# IZU2023_computerboard_ver1.net
KiCad netlist of a schematic drawn in EAGLE
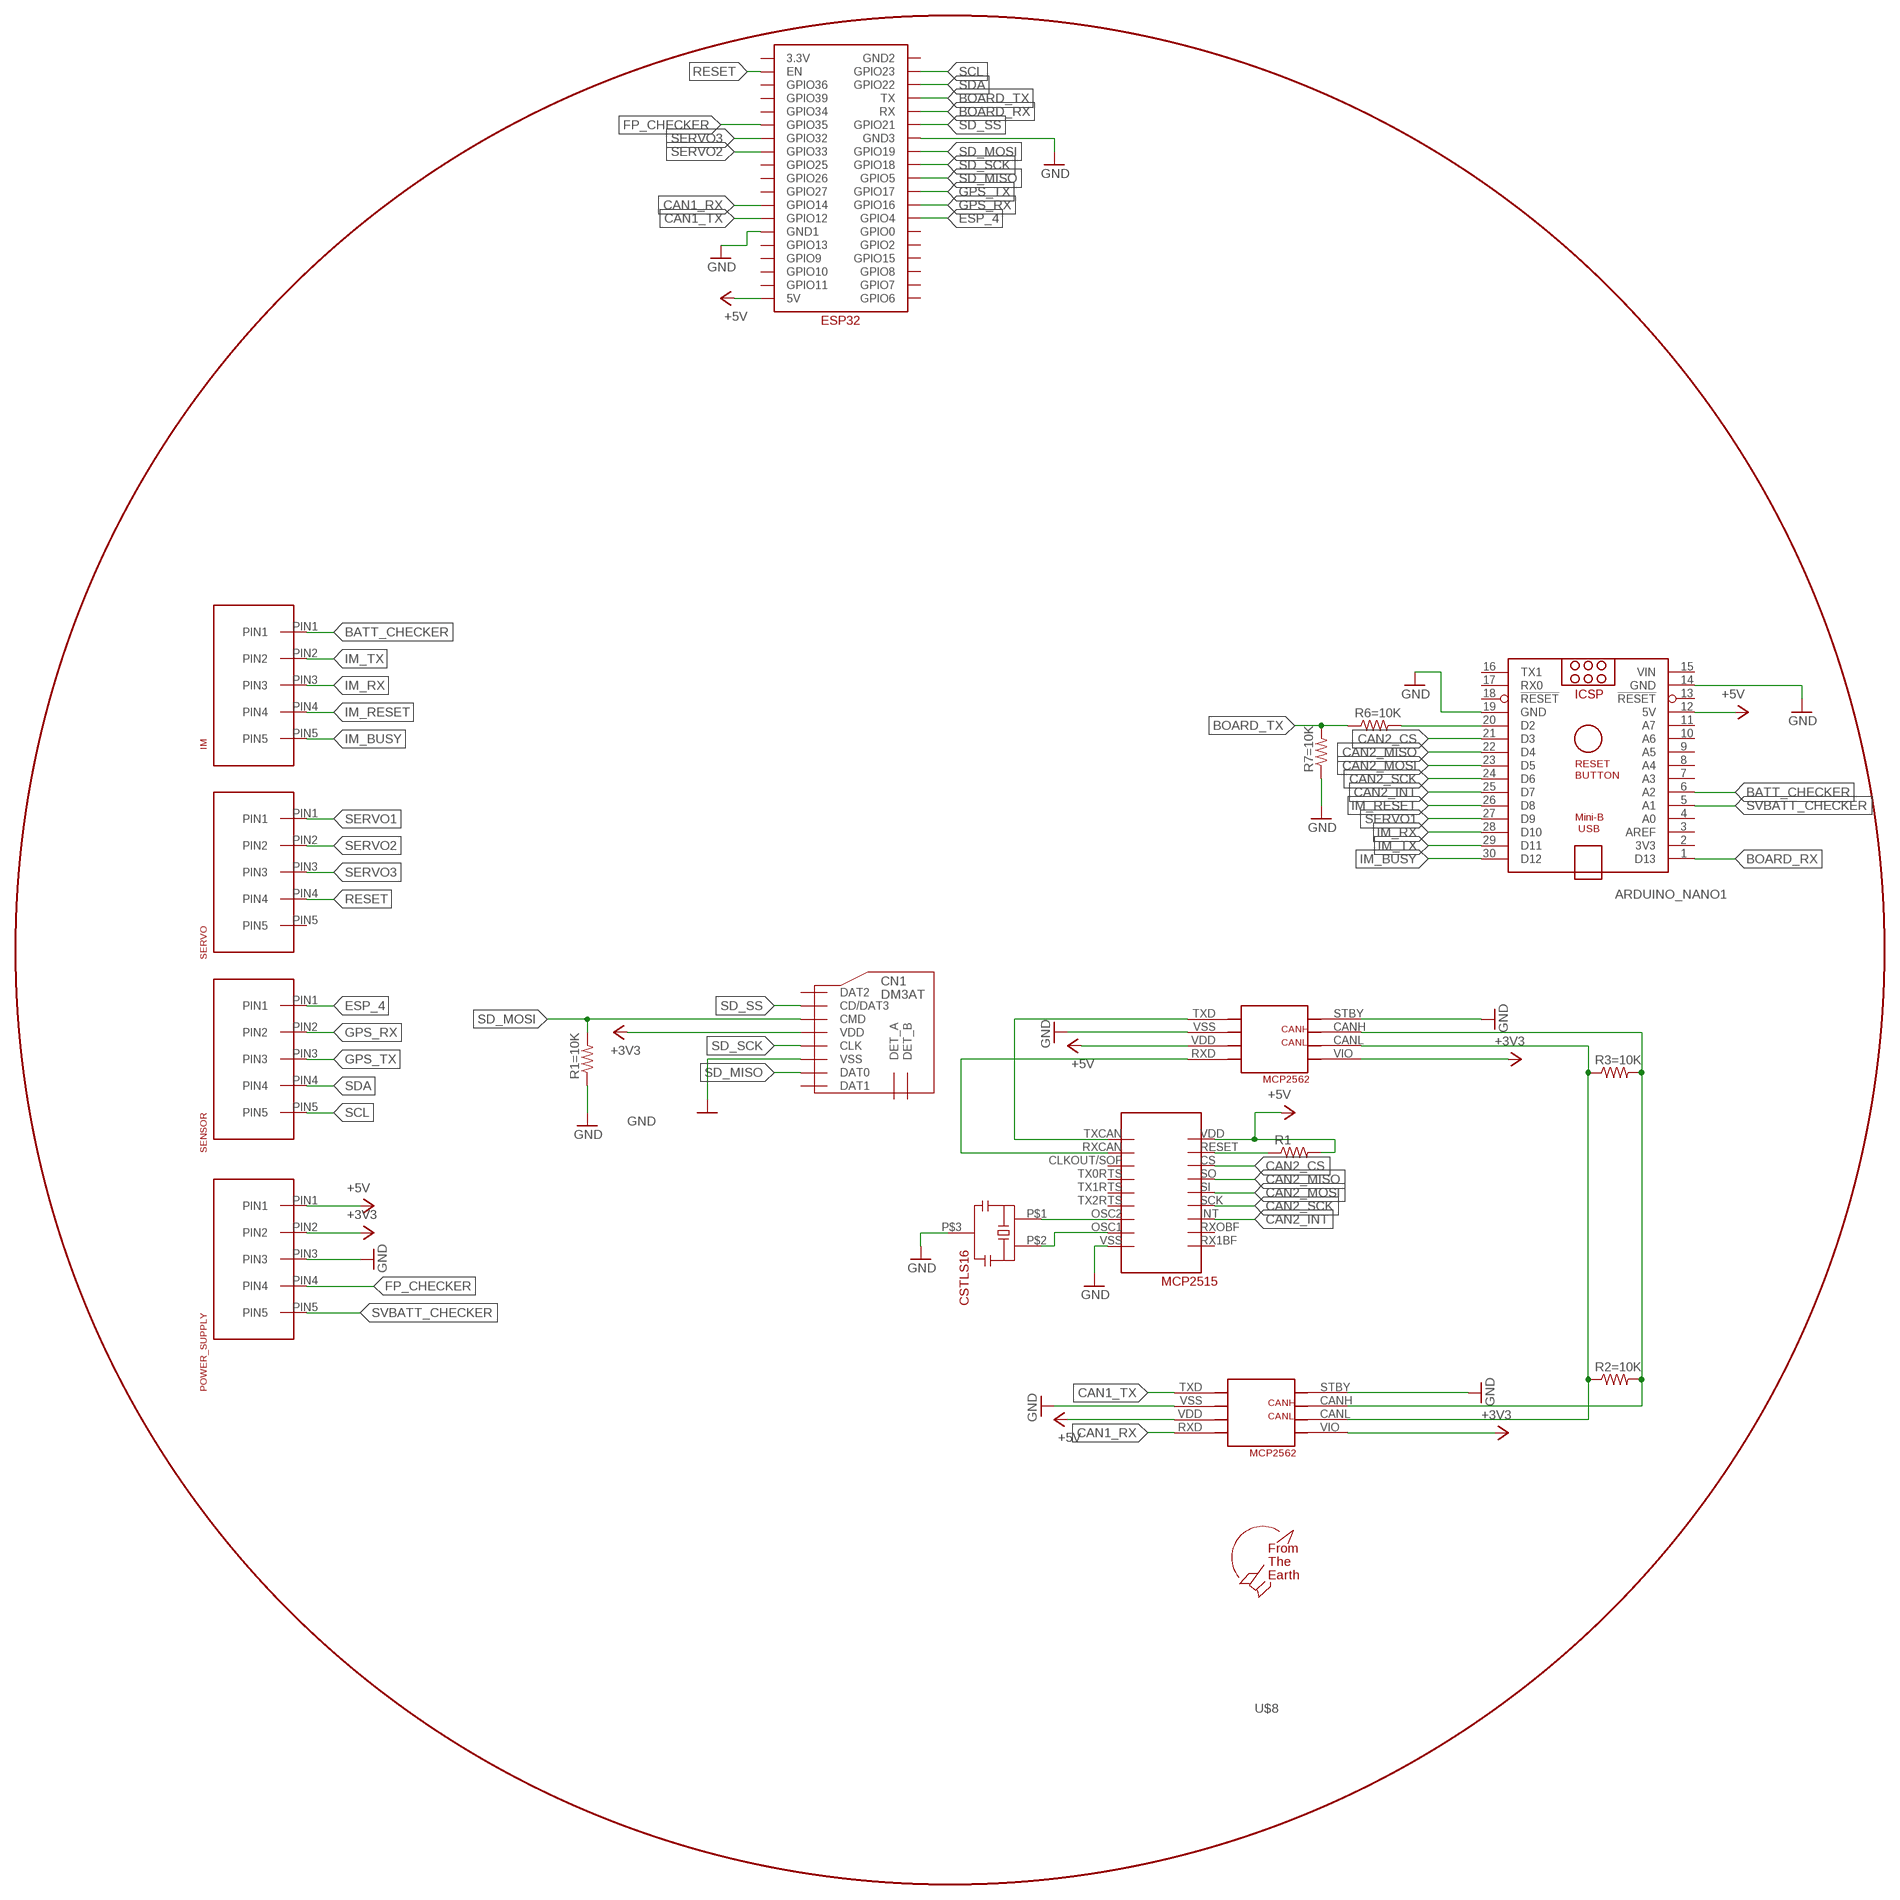
[diagram p0: schematic, sheet 1]

(export (version "E")
  (design (tool "Eeschema 10.0.6"))
  (components
    (comp (ref "ARDUINO_NANO1")
      (value "ARDUINO_NANO")
      (footprint "eagle-import:ARDUINO_NANO")
      (libsource (lib "eagle-import") (part "ARDUINO_NANO"))
    )
    (comp (ref "CN1")
      (value "DM3AT")
      (footprint "eagle-import:DM3AT")
      (libsource (lib "eagle-import") (part "DM3AT"))
    )
    (comp (ref "IM")
      (value "5PIN")
      (footprint "eagle-import:5PIN")
      (libsource (lib "eagle-import") (part "5PIN"))
    )
    (comp (ref "POWER_SUPPLY")
      (value "5PIN")
      (footprint "eagle-import:5PIN")
      (libsource (lib "eagle-import") (part "5PIN"))
    )
    (comp (ref "R1")
      (value "R-US_0204/7")
      (footprint "eagle-import:0204_7")
      (libsource (lib "eagle-import") (part "R-US_0204/7"))
    )
    (comp (ref "R1=10K")
      (value "R-US_0204/7")
      (footprint "eagle-import:0204_7")
      (libsource (lib "eagle-import") (part "R-US_0204/7"))
    )
    (comp (ref "R2=10K")
      (value "R-US_0204/7")
      (footprint "eagle-import:0204_7")
      (libsource (lib "eagle-import") (part "R-US_0204/7"))
    )
    (comp (ref "R3=10K")
      (value "R-US_0204/7")
      (footprint "eagle-import:0204_7")
      (libsource (lib "eagle-import") (part "R-US_0204/7"))
    )
    (comp (ref "R6=10K")
      (value "R-US_0204/7")
      (footprint "eagle-import:0204_7")
      (libsource (lib "eagle-import") (part "R-US_0204/7"))
    )
    (comp (ref "R7=10K")
      (value "R-US_0204/7")
      (footprint "eagle-import:0204_7")
      (libsource (lib "eagle-import") (part "R-US_0204/7"))
    )
    (comp (ref "SENSOR")
      (value "5PIN")
      (footprint "eagle-import:5PIN")
      (libsource (lib "eagle-import") (part "5PIN"))
    )
    (comp (ref "SERVO")
      (value "5PIN")
      (footprint "eagle-import:5PIN")
      (libsource (lib "eagle-import") (part "5PIN"))
    )
    (comp (ref "U$2")
      (value "MCP2515")
      (footprint "eagle-import:MCP2515")
      (libsource (lib "eagle-import") (part "MCP2515"))
    )
    (comp (ref "U$3")
      (value "MCP2562")
      (footprint "eagle-import:MCP2562")
      (libsource (lib "eagle-import") (part "MCP2562"))
    )
    (comp (ref "U$4")
      (value "MCP2562")
      (footprint "eagle-import:MCP2562")
      (libsource (lib "eagle-import") (part "MCP2562"))
    )
    (comp (ref "U$5")
      (value "CSTLS16")
      (footprint "eagle-import:CSTLS16")
      (libsource (lib "eagle-import") (part "CSTLS16"))
    )
    (comp (ref "U$7")
      (value "ESP32_ESP32")
      (footprint "eagle-import:ESP32_ESP32")
      (libsource (lib "eagle-import") (part "ESP32_ESP32"))
    )
    (comp (ref "U$8")
      (value "F.T.E.LOGO")
      (footprint "eagle-import:LOGO")
      (libsource (lib "eagle-import") (part "F.T.E.LOGO"))
    )
  )
  (nets
    (net (code "1") (name "+3V3") (class "Default")
      (node (ref "CN1") (pin "VDD") (pinfunction "VDD_VDD") (pintype "bidirectional"))
      (node (ref "POWER_SUPPLY") (pin "PIN2") (pinfunction "PIN2_PIN2") (pintype "bidirectional"))
      (node (ref "U$3") (pin "VIO") (pinfunction "VIO_VIO") (pintype "bidirectional"))
      (node (ref "U$4") (pin "VIO") (pinfunction "VIO_VIO") (pintype "bidirectional"))
    )
    (net (code "2") (name "+5V") (class "Default")
      (node (ref "ARDUINO_NANO1") (pin "12") (pinfunction "5V_12") (pintype "power_in"))
      (node (ref "POWER_SUPPLY") (pin "PIN1") (pinfunction "PIN1_PIN1") (pintype "bidirectional"))
      (node (ref "R1") (pin "2") (pinfunction "2_2") (pintype "passive"))
      (node (ref "U$2") (pin "VDD") (pinfunction "VDD_VDD") (pintype "bidirectional"))
      (node (ref "U$3") (pin "VDD") (pinfunction "VDD_VDD") (pintype "bidirectional"))
      (node (ref "U$4") (pin "VDD") (pinfunction "VDD_VDD") (pintype "bidirectional"))
      (node (ref "U$7") (pin "5V") (pinfunction "5V_5V") (pintype "bidirectional"))
    )
    (net (code "3") (name "/VIN") (class "Default")
      (node (ref "ARDUINO_NANO1") (pin "15") (pinfunction "VIN_15") (pintype "power_in"))
    )
    (net (code "4") (name "BATT_CHECKER") (class "Default")
      (node (ref "ARDUINO_NANO1") (pin "6") (pinfunction "A2_6") (pintype "bidirectional"))
      (node (ref "IM") (pin "PIN1") (pinfunction "PIN1_PIN1") (pintype "bidirectional"))
    )
    (net (code "5") (name "BOARD_RX") (class "Default")
      (node (ref "ARDUINO_NANO1") (pin "1") (pinfunction "D13_1") (pintype "bidirectional"))
      (node (ref "U$7") (pin "RX") (pinfunction "RX_RX") (pintype "bidirectional"))
    )
    (net (code "6") (name "BOARD_TX") (class "Default")
      (node (ref "R6=10K") (pin "1") (pinfunction "1_1") (pintype "passive"))
      (node (ref "R7=10K") (pin "2") (pinfunction "2_2") (pintype "passive"))
      (node (ref "U$7") (pin "TX") (pinfunction "TX_TX") (pintype "bidirectional"))
    )
    (net (code "7") (name "CAN1_RX") (class "Default")
      (node (ref "U$3") (pin "RXD") (pinfunction "RXD_RXD") (pintype "bidirectional"))
      (node (ref "U$7") (pin "GPIO14") (pinfunction "GPIO14_GPIO14") (pintype "bidirectional"))
    )
    (net (code "8") (name "CAN1_TX") (class "Default")
      (node (ref "U$3") (pin "TXD") (pinfunction "TXD_TXD") (pintype "bidirectional"))
      (node (ref "U$7") (pin "GPIO12") (pinfunction "GPIO12_GPIO12") (pintype "bidirectional"))
    )
    (net (code "9") (name "CAN2_CS") (class "Default")
      (node (ref "ARDUINO_NANO1") (pin "21") (pinfunction "D3_21") (pintype "bidirectional"))
      (node (ref "U$2") (pin "CS") (pinfunction "CS_CS") (pintype "bidirectional"))
    )
    (net (code "10") (name "CAN2_INT") (class "Default")
      (node (ref "ARDUINO_NANO1") (pin "25") (pinfunction "D7_25") (pintype "bidirectional"))
      (node (ref "U$2") (pin "INT") (pinfunction "INT_INT") (pintype "bidirectional"))
    )
    (net (code "11") (name "CAN2_MISO") (class "Default")
      (node (ref "ARDUINO_NANO1") (pin "22") (pinfunction "D4_22") (pintype "bidirectional"))
      (node (ref "U$2") (pin "SO") (pinfunction "SO_SO") (pintype "bidirectional"))
    )
    (net (code "12") (name "CAN2_MOSI") (class "Default")
      (node (ref "ARDUINO_NANO1") (pin "23") (pinfunction "D5_23") (pintype "bidirectional"))
      (node (ref "U$2") (pin "SI") (pinfunction "SI_SI") (pintype "bidirectional"))
    )
    (net (code "13") (name "CAN2_SCK") (class "Default")
      (node (ref "ARDUINO_NANO1") (pin "24") (pinfunction "D6_24") (pintype "bidirectional"))
      (node (ref "U$2") (pin "SCK") (pinfunction "SCK_SCK") (pintype "bidirectional"))
    )
    (net (code "14") (name "ESP_4") (class "Default")
      (node (ref "SENSOR") (pin "PIN1") (pinfunction "PIN1_PIN1") (pintype "bidirectional"))
      (node (ref "U$7") (pin "GPIO4") (pinfunction "GPIO4_GPIO4") (pintype "bidirectional"))
    )
    (net (code "15") (name "FP_CHECKER") (class "Default")
      (node (ref "POWER_SUPPLY") (pin "PIN4") (pinfunction "PIN4_PIN4") (pintype "bidirectional"))
      (node (ref "U$7") (pin "GPIO35") (pinfunction "GPIO35_GPIO35") (pintype "bidirectional"))
    )
    (net (code "16") (name "GND") (class "Default")
      (node (ref "ARDUINO_NANO1") (pin "14") (pinfunction "GND_14") (pintype "power_in"))
      (node (ref "ARDUINO_NANO1") (pin "19") (pinfunction "GND_19") (pintype "power_in"))
      (node (ref "CN1") (pin "VSS") (pinfunction "VSS_VSS") (pintype "bidirectional"))
      (node (ref "POWER_SUPPLY") (pin "PIN3") (pinfunction "PIN3_PIN3") (pintype "bidirectional"))
      (node (ref "R1=10K") (pin "1") (pinfunction "1_1") (pintype "passive"))
      (node (ref "R7=10K") (pin "1") (pinfunction "1_1") (pintype "passive"))
      (node (ref "U$2") (pin "VSS") (pinfunction "VSS_VSS") (pintype "bidirectional"))
      (node (ref "U$3") (pin "STBY") (pinfunction "STBY_STBY") (pintype "bidirectional"))
      (node (ref "U$3") (pin "VSS") (pinfunction "VSS_VSS") (pintype "bidirectional"))
      (node (ref "U$4") (pin "STBY") (pinfunction "STBY_STBY") (pintype "bidirectional"))
      (node (ref "U$4") (pin "VSS") (pinfunction "VSS_VSS") (pintype "bidirectional"))
      (node (ref "U$5") (pin "P$3") (pinfunction "P$3_P$3") (pintype "bidirectional"))
      (node (ref "U$7") (pin "GND1") (pinfunction "GND1_GND1") (pintype "bidirectional"))
      (node (ref "U$7") (pin "GND3") (pinfunction "GND3_GND3") (pintype "bidirectional"))
    )
    (net (code "17") (name "GPS_RX") (class "Default")
      (node (ref "SENSOR") (pin "PIN2") (pinfunction "PIN2_PIN2") (pintype "bidirectional"))
      (node (ref "U$7") (pin "GPIO16") (pinfunction "GPIO16_GPIO16") (pintype "bidirectional"))
    )
    (net (code "18") (name "GPS_TX") (class "Default")
      (node (ref "SENSOR") (pin "PIN3") (pinfunction "PIN3_PIN3") (pintype "bidirectional"))
      (node (ref "U$7") (pin "GPIO17") (pinfunction "GPIO17_GPIO17") (pintype "bidirectional"))
    )
    (net (code "19") (name "IM_BUSY") (class "Default")
      (node (ref "ARDUINO_NANO1") (pin "30") (pinfunction "D12_30") (pintype "bidirectional"))
      (node (ref "IM") (pin "PIN5") (pinfunction "PIN5_PIN5") (pintype "bidirectional"))
    )
    (net (code "20") (name "IM_RESET") (class "Default")
      (node (ref "ARDUINO_NANO1") (pin "26") (pinfunction "D8_26") (pintype "bidirectional"))
      (node (ref "IM") (pin "PIN4") (pinfunction "PIN4_PIN4") (pintype "bidirectional"))
    )
    (net (code "21") (name "IM_RX") (class "Default")
      (node (ref "ARDUINO_NANO1") (pin "28") (pinfunction "D10_28") (pintype "bidirectional"))
      (node (ref "IM") (pin "PIN3") (pinfunction "PIN3_PIN3") (pintype "bidirectional"))
    )
    (net (code "22") (name "IM_TX") (class "Default")
      (node (ref "ARDUINO_NANO1") (pin "29") (pinfunction "D11_29") (pintype "bidirectional"))
      (node (ref "IM") (pin "PIN2") (pinfunction "PIN2_PIN2") (pintype "bidirectional"))
    )
    (net (code "23") (name "Net-(ARDUINO_NANO1-D2)") (class "Default")
      (node (ref "ARDUINO_NANO1") (pin "20") (pinfunction "D2_20") (pintype "bidirectional"))
      (node (ref "R6=10K") (pin "2") (pinfunction "2_2") (pintype "passive"))
    )
    (net (code "24") (name "Net-(R1-Pad1)") (class "Default")
      (node (ref "R1") (pin "1") (pinfunction "1_1") (pintype "passive"))
      (node (ref "U$2") (pin "RESET") (pinfunction "RESET_RESET") (pintype "bidirectional"))
    )
    (net (code "25") (name "Net-(R2=10K-Pad1)") (class "Default")
      (node (ref "R2=10K") (pin "1") (pinfunction "1_1") (pintype "passive"))
      (node (ref "R3=10K") (pin "1") (pinfunction "1_1") (pintype "passive"))
      (node (ref "U$3") (pin "CANL") (pinfunction "CANL_CANL") (pintype "bidirectional"))
      (node (ref "U$4") (pin "CANL") (pinfunction "CANL_CANL") (pintype "bidirectional"))
    )
    (net (code "26") (name "Net-(R2=10K-Pad2)") (class "Default")
      (node (ref "R2=10K") (pin "2") (pinfunction "2_2") (pintype "passive"))
      (node (ref "R3=10K") (pin "2") (pinfunction "2_2") (pintype "passive"))
      (node (ref "U$3") (pin "CANH") (pinfunction "CANH_CANH") (pintype "bidirectional"))
      (node (ref "U$4") (pin "CANH") (pinfunction "CANH_CANH") (pintype "bidirectional"))
    )
    (net (code "27") (name "Net-(U$2-PadOSC1)") (class "Default")
      (node (ref "U$2") (pin "OSC1") (pinfunction "OSC1_OSC1") (pintype "bidirectional"))
      (node (ref "U$5") (pin "P$2") (pinfunction "P$2_P$2") (pintype "bidirectional"))
    )
    (net (code "28") (name "Net-(U$2-PadOSC2)") (class "Default")
      (node (ref "U$2") (pin "OSC2") (pinfunction "OSC2_OSC2") (pintype "bidirectional"))
      (node (ref "U$5") (pin "P$1") (pinfunction "P$1_P$1") (pintype "bidirectional"))
    )
    (net (code "29") (name "Net-(U$2-PadRXCAN)") (class "Default")
      (node (ref "U$2") (pin "RXCAN") (pinfunction "RXCAN_RXCAN") (pintype "bidirectional"))
      (node (ref "U$4") (pin "RXD") (pinfunction "RXD_RXD") (pintype "bidirectional"))
    )
    (net (code "30") (name "Net-(U$2-PadTXCAN)") (class "Default")
      (node (ref "U$2") (pin "TXCAN") (pinfunction "TXCAN_TXCAN") (pintype "bidirectional"))
      (node (ref "U$4") (pin "TXD") (pinfunction "TXD_TXD") (pintype "bidirectional"))
    )
    (net (code "31") (name "RESET") (class "Default")
      (node (ref "SERVO") (pin "PIN4") (pinfunction "PIN4_PIN4") (pintype "bidirectional"))
      (node (ref "U$7") (pin "EN") (pinfunction "EN_EN") (pintype "bidirectional"))
    )
    (net (code "32") (name "SCL") (class "Default")
      (node (ref "SENSOR") (pin "PIN5") (pinfunction "PIN5_PIN5") (pintype "bidirectional"))
      (node (ref "U$7") (pin "GPIO23") (pinfunction "GPIO23_GPIO23") (pintype "bidirectional"))
    )
    (net (code "33") (name "SDA") (class "Default")
      (node (ref "SENSOR") (pin "PIN4") (pinfunction "PIN4_PIN4") (pintype "bidirectional"))
      (node (ref "U$7") (pin "GPIO22") (pinfunction "GPIO22_GPIO22") (pintype "bidirectional"))
    )
    (net (code "34") (name "SD_MISO") (class "Default")
      (node (ref "CN1") (pin "DAT0") (pinfunction "DAT0_DAT0") (pintype "bidirectional"))
      (node (ref "U$7") (pin "GPIO5") (pinfunction "GPIO5_GPIO5") (pintype "bidirectional"))
    )
    (net (code "35") (name "SD_MOSI") (class "Default")
      (node (ref "CN1") (pin "CMD") (pinfunction "CMD_CMD") (pintype "bidirectional"))
      (node (ref "R1=10K") (pin "2") (pinfunction "2_2") (pintype "passive"))
      (node (ref "U$7") (pin "GPIO19") (pinfunction "GPIO19_GPIO19") (pintype "bidirectional"))
    )
    (net (code "36") (name "SD_SCK") (class "Default")
      (node (ref "CN1") (pin "CLK") (pinfunction "CLK_CLK") (pintype "bidirectional"))
      (node (ref "U$7") (pin "GPIO18") (pinfunction "GPIO18_GPIO18") (pintype "bidirectional"))
    )
    (net (code "37") (name "SD_SS") (class "Default")
      (node (ref "CN1") (pin "CD/DAT3") (pinfunction "CD/DAT3_CD/DAT3") (pintype "bidirectional"))
      (node (ref "U$7") (pin "GPIO21") (pinfunction "GPIO21_GPIO21") (pintype "bidirectional"))
    )
    (net (code "38") (name "SERVO1") (class "Default")
      (node (ref "ARDUINO_NANO1") (pin "27") (pinfunction "D9_27") (pintype "bidirectional"))
      (node (ref "SERVO") (pin "PIN1") (pinfunction "PIN1_PIN1") (pintype "bidirectional"))
    )
    (net (code "39") (name "SERVO2") (class "Default")
      (node (ref "SERVO") (pin "PIN2") (pinfunction "PIN2_PIN2") (pintype "bidirectional"))
      (node (ref "U$7") (pin "GPIO33") (pinfunction "GPIO33_GPIO33") (pintype "bidirectional"))
    )
    (net (code "40") (name "SERVO3") (class "Default")
      (node (ref "SERVO") (pin "PIN3") (pinfunction "PIN3_PIN3") (pintype "bidirectional"))
      (node (ref "U$7") (pin "GPIO32") (pinfunction "GPIO32_GPIO32") (pintype "bidirectional"))
    )
    (net (code "41") (name "SVBATT_CHECKER") (class "Default")
      (node (ref "ARDUINO_NANO1") (pin "5") (pinfunction "A1_5") (pintype "bidirectional"))
      (node (ref "POWER_SUPPLY") (pin "PIN5") (pinfunction "PIN5_PIN5") (pintype "bidirectional"))
    )
    (net (code "42") (name "unconnected-(ARDUINO_NANO1-3V3-Pad2)") (class "Default")
      (node (ref "ARDUINO_NANO1") (pin "2") (pinfunction "3V3_2") (pintype "output"))
    )
    (net (code "43") (name "unconnected-(ARDUINO_NANO1-A0-Pad4)") (class "Default")
      (node (ref "ARDUINO_NANO1") (pin "4") (pinfunction "A0_4") (pintype "bidirectional"))
    )
    (net (code "44") (name "unconnected-(ARDUINO_NANO1-A3-Pad7)") (class "Default")
      (node (ref "ARDUINO_NANO1") (pin "7") (pinfunction "A3_7") (pintype "bidirectional"))
    )
    (net (code "45") (name "unconnected-(ARDUINO_NANO1-A4-Pad8)") (class "Default")
      (node (ref "ARDUINO_NANO1") (pin "8") (pinfunction "A4_8") (pintype "bidirectional"))
    )
    (net (code "46") (name "unconnected-(ARDUINO_NANO1-A5-Pad9)") (class "Default")
      (node (ref "ARDUINO_NANO1") (pin "9") (pinfunction "A5_9") (pintype "bidirectional"))
    )
    (net (code "47") (name "unconnected-(ARDUINO_NANO1-A6-Pad10)") (class "Default")
      (node (ref "ARDUINO_NANO1") (pin "10") (pinfunction "A6_10") (pintype "bidirectional"))
    )
    (net (code "48") (name "unconnected-(ARDUINO_NANO1-A7-Pad11)") (class "Default")
      (node (ref "ARDUINO_NANO1") (pin "11") (pinfunction "A7_11") (pintype "bidirectional"))
    )
    (net (code "49") (name "unconnected-(ARDUINO_NANO1-AREF-Pad3)") (class "Default")
      (node (ref "ARDUINO_NANO1") (pin "3") (pinfunction "AREF_3") (pintype "input"))
    )
    (net (code "50") (name "unconnected-(ARDUINO_NANO1-RX0-Pad17)") (class "Default")
      (node (ref "ARDUINO_NANO1") (pin "17") (pinfunction "RX0_17") (pintype "bidirectional"))
    )
    (net (code "51") (name "unconnected-(ARDUINO_NANO1-TX1-Pad16)") (class "Default")
      (node (ref "ARDUINO_NANO1") (pin "16") (pinfunction "TX1_16") (pintype "bidirectional"))
    )
    (net (code "52") (name "unconnected-(ARDUINO_NANO1-~{RESET}-Pad13)") (class "Default")
      (node (ref "ARDUINO_NANO1") (pin "13") (pinfunction "~{RESET}_13") (pintype "input"))
    )
    (net (code "53") (name "unconnected-(ARDUINO_NANO1-~{RESET}-Pad18)") (class "Default")
      (node (ref "ARDUINO_NANO1") (pin "18") (pinfunction "~{RESET}_18") (pintype "input"))
    )
    (net (code "54") (name "unconnected-(CN1-PadDAT1)") (class "Default")
      (node (ref "CN1") (pin "DAT1") (pinfunction "DAT1_DAT1") (pintype "bidirectional"))
    )
    (net (code "55") (name "unconnected-(CN1-PadDAT2)") (class "Default")
      (node (ref "CN1") (pin "DAT2") (pinfunction "DAT2_DAT2") (pintype "bidirectional"))
    )
    (net (code "56") (name "unconnected-(CN1-PadDET_A)") (class "Default")
      (node (ref "CN1") (pin "DET_A") (pinfunction "DET_A_DET_A") (pintype "bidirectional"))
    )
    (net (code "57") (name "unconnected-(CN1-PadDET_B)") (class "Default")
      (node (ref "CN1") (pin "DET_B") (pinfunction "DET_B_DET_B") (pintype "bidirectional"))
    )
    (net (code "58") (name "unconnected-(SERVO-PadPIN5)") (class "Default")
      (node (ref "SERVO") (pin "PIN5") (pinfunction "PIN5_PIN5") (pintype "bidirectional"))
    )
    (net (code "59") (name "unconnected-(U$2-PadCLKOUT{slash}SOF)") (class "Default")
      (node (ref "U$2") (pin "CLKOUT/SOF") (pinfunction "CLKOUT/SOF_CLKOUT/SOF") (pintype "bidirectional"))
    )
    (net (code "60") (name "unconnected-(U$2-PadRX1BF)") (class "Default")
      (node (ref "U$2") (pin "RX1BF") (pinfunction "RX1BF_RX1BF") (pintype "bidirectional"))
    )
    (net (code "61") (name "unconnected-(U$2-PadTX0RTS)") (class "Default")
      (node (ref "U$2") (pin "TX0RTS") (pinfunction "TX0RTS_TX0RTS") (pintype "bidirectional"))
    )
    (net (code "62") (name "unconnected-(U$2-PadTX1RTS)") (class "Default")
      (node (ref "U$2") (pin "TX1RTS") (pinfunction "TX1RTS_TX1RTS") (pintype "bidirectional"))
    )
    (net (code "63") (name "unconnected-(U$2-PadTX2RTS)") (class "Default")
      (node (ref "U$2") (pin "TX2RTS") (pinfunction "TX2RTS_TX2RTS") (pintype "bidirectional"))
    )
    (net (code "64") (name "unconnected-(U$2-RX0BF-PadRXOBF)") (class "Default")
      (node (ref "U$2") (pin "RXOBF") (pinfunction "RX0BF_RXOBF") (pintype "bidirectional"))
    )
    (net (code "65") (name "unconnected-(U$7-Pad3.3V)") (class "Default")
      (node (ref "U$7") (pin "3.3V") (pinfunction "3.3V_3.3V") (pintype "bidirectional"))
    )
    (net (code "66") (name "unconnected-(U$7-PadGND2)") (class "Default")
      (node (ref "U$7") (pin "GND2") (pinfunction "GND2_GND2") (pintype "bidirectional"))
    )
    (net (code "67") (name "unconnected-(U$7-PadGPIO0)") (class "Default")
      (node (ref "U$7") (pin "GPIO0") (pinfunction "GPIO0_GPIO0") (pintype "bidirectional"))
    )
    (net (code "68") (name "unconnected-(U$7-PadGPIO2)") (class "Default")
      (node (ref "U$7") (pin "GPIO2") (pinfunction "GPIO2_GPIO2") (pintype "bidirectional"))
    )
    (net (code "69") (name "unconnected-(U$7-PadGPIO6)") (class "Default")
      (node (ref "U$7") (pin "GPIO6") (pinfunction "GPIO6_GPIO6") (pintype "bidirectional"))
    )
    (net (code "70") (name "unconnected-(U$7-PadGPIO7)") (class "Default")
      (node (ref "U$7") (pin "GPIO7") (pinfunction "GPIO7_GPIO7") (pintype "bidirectional"))
    )
    (net (code "71") (name "unconnected-(U$7-PadGPIO8)") (class "Default")
      (node (ref "U$7") (pin "GPIO8") (pinfunction "GPIO8_GPIO8") (pintype "bidirectional"))
    )
    (net (code "72") (name "unconnected-(U$7-PadGPIO9)") (class "Default")
      (node (ref "U$7") (pin "GPIO9") (pinfunction "GPIO9_GPIO9") (pintype "bidirectional"))
    )
    (net (code "73") (name "unconnected-(U$7-PadGPIO10)") (class "Default")
      (node (ref "U$7") (pin "GPIO10") (pinfunction "GPIO10_GPIO10") (pintype "bidirectional"))
    )
    (net (code "74") (name "unconnected-(U$7-PadGPIO11)") (class "Default")
      (node (ref "U$7") (pin "GPIO11") (pinfunction "GPIO11_GPIO11") (pintype "bidirectional"))
    )
    (net (code "75") (name "unconnected-(U$7-PadGPIO13)") (class "Default")
      (node (ref "U$7") (pin "GPIO13") (pinfunction "GPIO13_GPIO13") (pintype "bidirectional"))
    )
    (net (code "76") (name "unconnected-(U$7-PadGPIO15)") (class "Default")
      (node (ref "U$7") (pin "GPIO15") (pinfunction "GPIO15_GPIO15") (pintype "bidirectional"))
    )
    (net (code "77") (name "unconnected-(U$7-PadGPIO25)") (class "Default")
      (node (ref "U$7") (pin "GPIO25") (pinfunction "GPIO25_GPIO25") (pintype "bidirectional"))
    )
    (net (code "78") (name "unconnected-(U$7-PadGPIO26)") (class "Default")
      (node (ref "U$7") (pin "GPIO26") (pinfunction "GPIO26_GPIO26") (pintype "bidirectional"))
    )
    (net (code "79") (name "unconnected-(U$7-PadGPIO27)") (class "Default")
      (node (ref "U$7") (pin "GPIO27") (pinfunction "GPIO27_GPIO27") (pintype "bidirectional"))
    )
    (net (code "80") (name "unconnected-(U$7-PadGPIO34)") (class "Default")
      (node (ref "U$7") (pin "GPIO34") (pinfunction "GPIO34_GPIO34") (pintype "bidirectional"))
    )
    (net (code "81") (name "unconnected-(U$7-PadGPIO36)") (class "Default")
      (node (ref "U$7") (pin "GPIO36") (pinfunction "GPIO36_GPIO36") (pintype "bidirectional"))
    )
    (net (code "82") (name "unconnected-(U$7-PadGPIO39)") (class "Default")
      (node (ref "U$7") (pin "GPIO39") (pinfunction "GPIO39_GPIO39") (pintype "bidirectional"))
    )
  )
)
